# i2c.net
KiCad netlist of a schematic drawn in Altium Designer
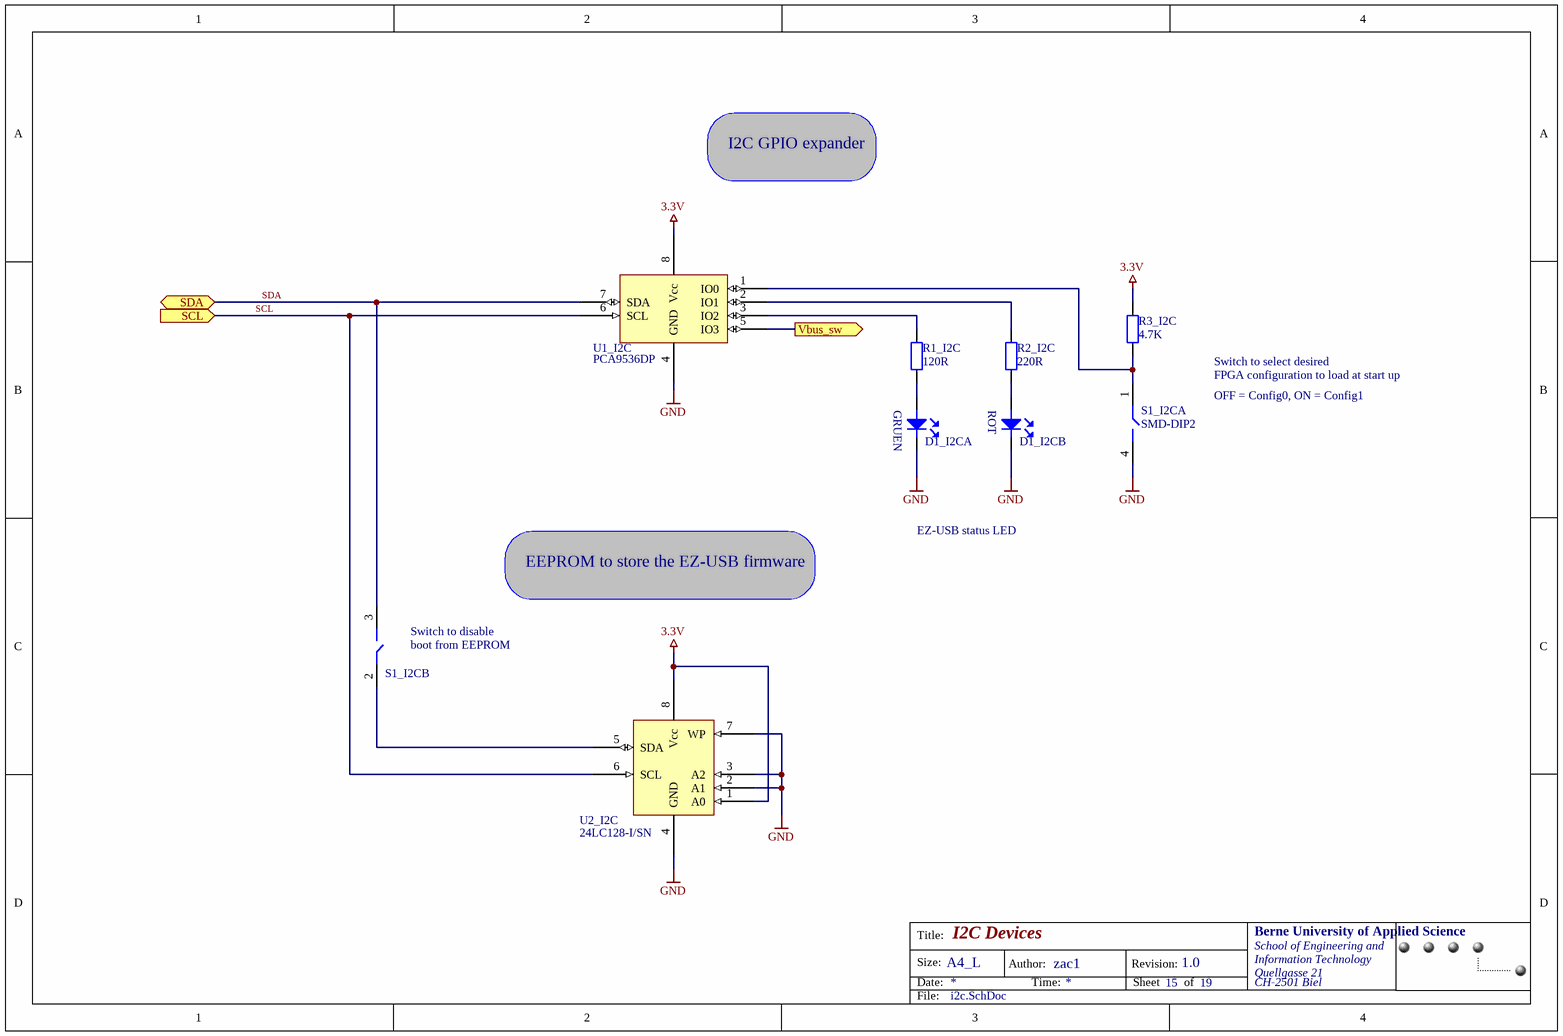
[diagram p0: i2c.SchDoc]

(export (version "E")
  (design (tool "Eeschema 10.0.6"))
  (components
    (comp (ref "D1_I2C")
      (value "1211C-LED")
      (footprint "stan-led4")
      (description "Stanley 1211C Bi-Color Ultra Compact SMT LED")
      (fields (field (name "MANUFACTURER") "Stanley") (field (name "PART NUMBER") "BRBG1211C"))
      (libsource (lib "gecko3-user") (part "1211C-LED"))
    )
    (comp (ref "R1_I2C")
      (value "120R")
      (footprint "0402")
      (description "Resistor")
      (fields
        (field (name "MANUFACTURER") "PHYCOMP")
        (field (name "PART NUMBER") "232270671201")
        (field (name "PUBLISHER") "Altium Limited")
      )
      (libsource (lib "Miscellaneous Devices") (part "Res2"))
    )
    (comp (ref "R2_I2C")
      (value "220R")
      (footprint "0402")
      (description "Resistor")
      (fields
        (field (name "MANUFACTURER") "PHYCOMP")
        (field (name "PART NUMBER") "232270672201")
        (field (name "PUBLISHER") "Altium Limited")
      )
      (libsource (lib "Miscellaneous Devices") (part "Res2"))
    )
    (comp (ref "R3_I2C")
      (value "4.7K")
      (footprint "0402")
      (description "Resistor")
      (fields
        (field (name "MANUFACTURER") "PHYCOMP")
        (field (name "PART NUMBER") "232270674702")
        (field (name "PUBLISHER") "Altium Limited")
      )
      (libsource (lib "Miscellaneous Devices") (part "Res2"))
    )
    (comp (ref "S1_I2C")
      (value "SMD-DIP2")
      (footprint "MINIDIP2")
      (fields
        (field (name "MANUFACTURER") "TYCO")
        (field (name "PART NUMBER") "GDH02S")
        (field (name "Comment") "SW-DIP2")
      )
      (libsource (lib "gecko3-user") (part "SW-DIP2"))
    )
    (comp (ref "U1_I2C")
      (value "PCA9536DP")
      (footprint "TSSO3X6-G8/X.3")
      (description "4-bit I2C I/O Port")
      (fields (field (name "MANUFACTURER") "TI") (field (name "PART NUMBER") "PCA9536DGKR"))
      (libsource (lib "gecko3-user") (part "PCA9536"))
    )
    (comp (ref "U2_I2C")
      (value "24LC128-I/SN")
      (footprint "SO-G8")
      (fields (field (name "MANUFACTURER") "Microchip"))
      (libsource (lib "gecko3-user") (part "24LC128-I/SN"))
    )
  )
  (nets
    (net (code "1") (name "/SCL") (class "Default")
      (node (ref "U1_I2C") (pin "6") (pinfunction "SCL_6") (pintype "input"))
      (node (ref "U2_I2C") (pin "6") (pinfunction "SCL_6") (pintype "input"))
    )
    (net (code "2") (name "/SDA") (class "Default")
      (node (ref "S1_I2C") (pin "3") (pinfunction "3_3") (pintype "passive"))
      (node (ref "U1_I2C") (pin "7") (pinfunction "SDA_7") (pintype "bidirectional"))
    )
    (net (code "3") (name "/Vbus_sw") (class "Default")
      (node (ref "U1_I2C") (pin "5") (pinfunction "IO3_5") (pintype "bidirectional"))
    )
    (net (code "4") (name "3.3V") (class "Default")
      (node (ref "R3_I2C") (pin "2") (pinfunction "2_2") (pintype "passive"))
      (node (ref "U1_I2C") (pin "8") (pinfunction "Vcc_8") (pintype "power_in"))
      (node (ref "U2_I2C") (pin "1") (pinfunction "A0_1") (pintype "input"))
      (node (ref "U2_I2C") (pin "8") (pinfunction "Vcc_8") (pintype "power_in"))
    )
    (net (code "5") (name "GND") (class "Default")
      (node (ref "D1_I2C") (pin "2") (pinfunction "K_2") (pintype "passive"))
      (node (ref "D1_I2C") (pin "4") (pinfunction "K_4") (pintype "passive"))
      (node (ref "S1_I2C") (pin "4") (pinfunction "4_4") (pintype "passive"))
      (node (ref "U1_I2C") (pin "4") (pinfunction "GND_4") (pintype "power_in"))
      (node (ref "U2_I2C") (pin "2") (pinfunction "A1_2") (pintype "input"))
      (node (ref "U2_I2C") (pin "3") (pinfunction "A2_3") (pintype "input"))
      (node (ref "U2_I2C") (pin "4") (pinfunction "GND_4") (pintype "power_in"))
      (node (ref "U2_I2C") (pin "7") (pinfunction "WP_7") (pintype "input"))
    )
    (net (code "6") (name "Net-(D1_I2CA-A)") (class "Default")
      (node (ref "D1_I2C") (pin "3") (pinfunction "A_3") (pintype "passive"))
      (node (ref "R1_I2C") (pin "1") (pinfunction "1_1") (pintype "passive"))
    )
    (net (code "7") (name "Net-(D1_I2CB-A)") (class "Default")
      (node (ref "D1_I2C") (pin "1") (pinfunction "A_1") (pintype "passive"))
      (node (ref "R2_I2C") (pin "1") (pinfunction "1_1") (pintype "passive"))
    )
    (net (code "8") (name "Net-(U1_I2C-IO0)") (class "Default")
      (node (ref "R3_I2C") (pin "1") (pinfunction "1_1") (pintype "passive"))
      (node (ref "S1_I2C") (pin "1") (pinfunction "1_1") (pintype "passive"))
      (node (ref "U1_I2C") (pin "1") (pinfunction "IO0_1") (pintype "bidirectional"))
    )
    (net (code "9") (name "Net-(U1_I2C-IO1)") (class "Default")
      (node (ref "R2_I2C") (pin "2") (pinfunction "2_2") (pintype "passive"))
      (node (ref "U1_I2C") (pin "2") (pinfunction "IO1_2") (pintype "bidirectional"))
    )
    (net (code "10") (name "Net-(U1_I2C-IO2)") (class "Default")
      (node (ref "R1_I2C") (pin "2") (pinfunction "2_2") (pintype "passive"))
      (node (ref "U1_I2C") (pin "3") (pinfunction "IO2_3") (pintype "bidirectional"))
    )
    (net (code "11") (name "Net-(U2_I2C-SDA)") (class "Default")
      (node (ref "S1_I2C") (pin "2") (pinfunction "2_2") (pintype "passive"))
      (node (ref "U2_I2C") (pin "5") (pinfunction "SDA_5") (pintype "bidirectional"))
    )
  )
)
